# strain-gauge-amplifier-v1.net
KiCad netlist of a schematic drawn in EAGLE
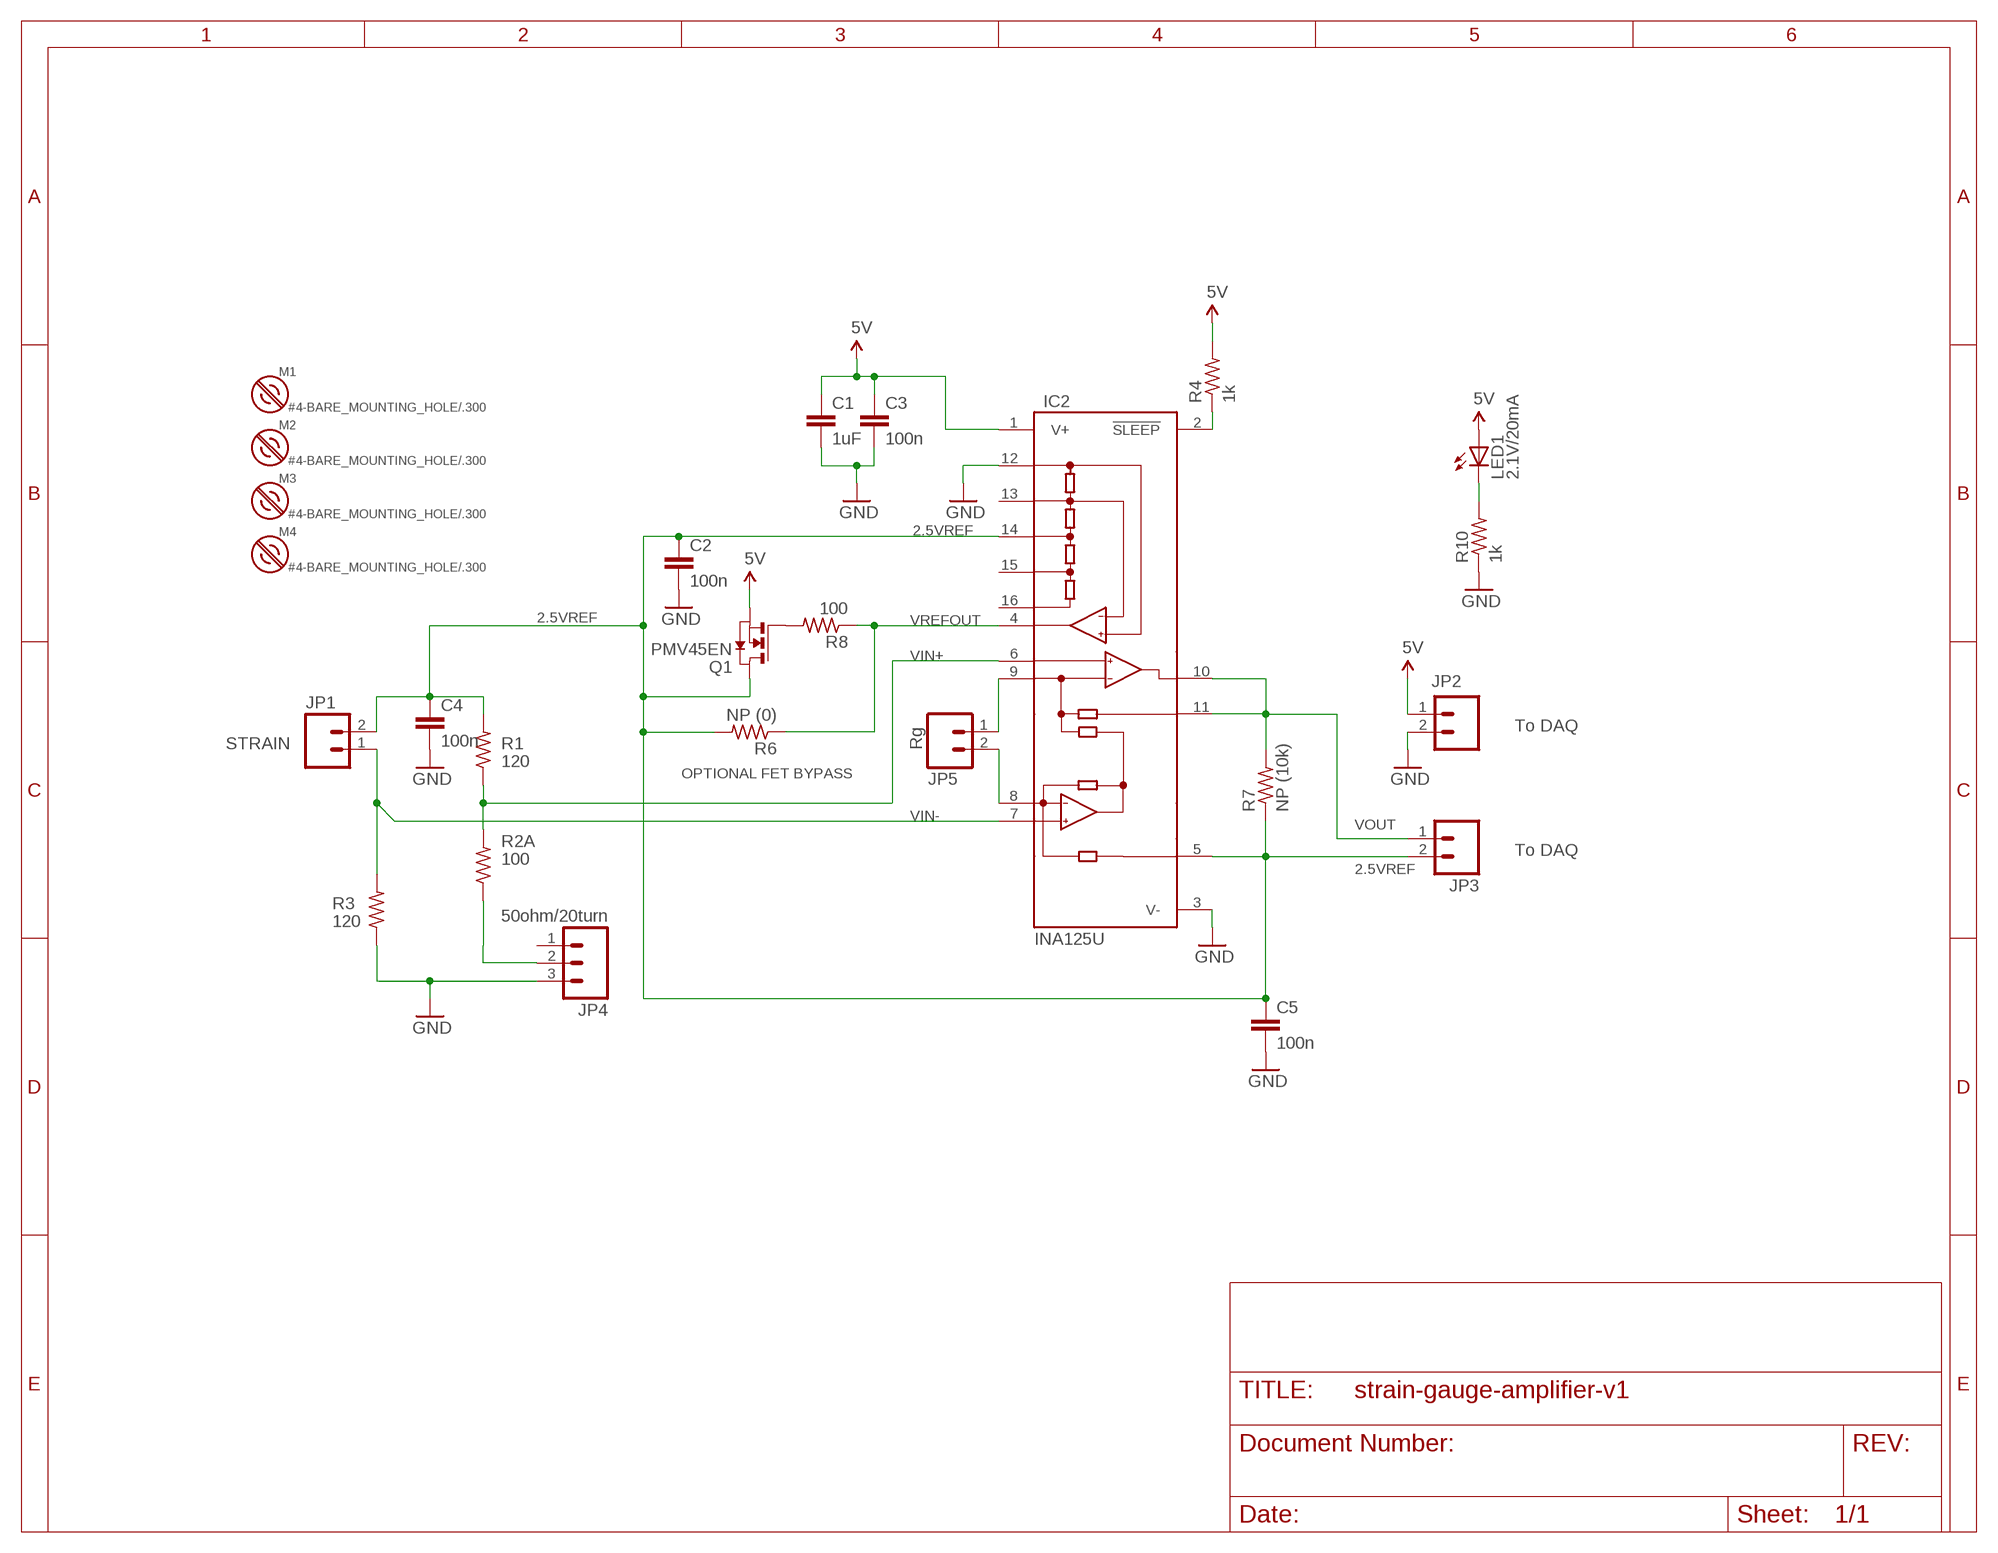
[diagram p0: schematic, sheet 1]

(export (version "E")
  (design (tool "Eeschema 10.0.6"))
  (components
    (comp (ref "C1")
      (value "1uF")
      (footprint "eagle-import:0805-C-NOSILK")
      (libsource (lib "eagle-import") (part "C-EU0805-C-NOSILK"))
    )
    (comp (ref "C2")
      (value "100n")
      (footprint "eagle-import:0805-C-NOSILK")
      (libsource (lib "eagle-import") (part "C-EU0805-C-NOSILK"))
    )
    (comp (ref "C3")
      (value "100n")
      (footprint "eagle-import:0805-C-NOSILK")
      (libsource (lib "eagle-import") (part "C-EU0805-C-NOSILK"))
    )
    (comp (ref "C4")
      (value "100n")
      (footprint "eagle-import:0805-C-NOSILK")
      (libsource (lib "eagle-import") (part "C-EU0805-C-NOSILK"))
    )
    (comp (ref "C5")
      (value "100n")
      (footprint "eagle-import:0805-C-NOSILK")
      (libsource (lib "eagle-import") (part "C-EU0805-C-NOSILK"))
    )
    (comp (ref "IC2")
      (value "INA125U")
      (footprint "eagle-import:SO16-1")
      (fields (field (name "MF") "TEXAS INSTRUMENT CONNECTORS"))
      (libsource (lib "eagle-import") (part "INA125U"))
    )
    (comp (ref "JP1")
      (value "STRAIN")
      (footprint "eagle-import:SCREWTERMINAL-5MM-2")
      (libsource (lib "eagle-import") (part "M025MM"))
    )
    (comp (ref "JP2")
      (value "M025MM")
      (footprint "eagle-import:SCREWTERMINAL-5MM-2")
      (libsource (lib "eagle-import") (part "M025MM"))
    )
    (comp (ref "JP3")
      (value "M025MM")
      (footprint "eagle-import:SCREWTERMINAL-5MM-2")
      (libsource (lib "eagle-import") (part "M025MM"))
    )
    (comp (ref "JP4")
      (value "50ohm/20turn")
      (footprint "eagle-import:1X03_NO_SILK")
      (libsource (lib "eagle-import") (part "M031X03_NO_SILK"))
    )
    (comp (ref "JP5")
      (value "Rg")
      (footprint "eagle-import:SCREWTERMINAL-5MM-2")
      (libsource (lib "eagle-import") (part "M025MM"))
    )
    (comp (ref "LED1")
      (value "2.1V/20mA")
      (footprint "eagle-import:LED-0603")
      (libsource (lib "eagle-import") (part "LED0603"))
    )
    (comp (ref "M1")
      (value "#4-BARE_MOUNTING_HOLE/.300")
      (footprint "eagle-import:#4_.300-BARE+STD_NUT_OR_STAR_WASHER")
      (libsource (lib "eagle-import") (part "#4-BARE_MOUNTING_HOLE/.300"))
    )
    (comp (ref "M2")
      (value "#4-BARE_MOUNTING_HOLE/.300")
      (footprint "eagle-import:#4_.300-BARE+STD_NUT_OR_STAR_WASHER")
      (libsource (lib "eagle-import") (part "#4-BARE_MOUNTING_HOLE/.300"))
    )
    (comp (ref "M3")
      (value "#4-BARE_MOUNTING_HOLE/.300")
      (footprint "eagle-import:#4_.300-BARE+STD_NUT_OR_STAR_WASHER")
      (libsource (lib "eagle-import") (part "#4-BARE_MOUNTING_HOLE/.300"))
    )
    (comp (ref "M4")
      (value "#4-BARE_MOUNTING_HOLE/.300")
      (footprint "eagle-import:#4_.300-BARE+STD_NUT_OR_STAR_WASHER")
      (libsource (lib "eagle-import") (part "#4-BARE_MOUNTING_HOLE/.300"))
    )
    (comp (ref "Q1")
      (value "PMV45EN")
      (footprint "eagle-import:SOT23")
      (libsource (lib "eagle-import") (part "PMV45EN"))
    )
    (comp (ref "R1")
      (value "120")
      (footprint "eagle-import:0805-C-NOSILK")
      (libsource (lib "eagle-import") (part "R-US_0805-C-NOSILK"))
    )
    (comp (ref "R2A")
      (value "100")
      (footprint "eagle-import:0805-C-NOSILK")
      (libsource (lib "eagle-import") (part "R-US_0805-C-NOSILK"))
    )
    (comp (ref "R3")
      (value "120")
      (footprint "eagle-import:0805-C-NOSILK")
      (libsource (lib "eagle-import") (part "R-US_0805-C-NOSILK"))
    )
    (comp (ref "R4")
      (value "1k")
      (footprint "eagle-import:0805-C-NOSILK")
      (libsource (lib "eagle-import") (part "R-US_0805-C-NOSILK"))
    )
    (comp (ref "R6")
      (value "NP (0)")
      (footprint "eagle-import:0805-C-NOSILK")
      (libsource (lib "eagle-import") (part "R-US_0805-C-NOSILK"))
    )
    (comp (ref "R7")
      (value "NP (10k)")
      (footprint "eagle-import:0805-C-NOSILK")
      (libsource (lib "eagle-import") (part "R-US_0805-C-NOSILK"))
    )
    (comp (ref "R8")
      (value "100")
      (footprint "eagle-import:0805-C-NOSILK")
      (libsource (lib "eagle-import") (part "R-US_0805-C-NOSILK"))
    )
    (comp (ref "R10")
      (value "1k")
      (footprint "eagle-import:0805-C-NOSILK")
      (libsource (lib "eagle-import") (part "R-US_0805-C-NOSILK"))
    )
  )
  (nets
    (net (code "1") (name "/2.5VREF") (class "Default")
      (node (ref "C2") (pin "1") (pinfunction "1_1") (pintype "passive"))
      (node (ref "C4") (pin "1") (pinfunction "1_1") (pintype "passive"))
      (node (ref "C5") (pin "1") (pinfunction "1_1") (pintype "passive"))
      (node (ref "IC2") (pin "14") (pinfunction "REF2.5_14") (pintype "output"))
      (node (ref "IC2") (pin "5") (pinfunction "REF_5") (pintype "passive"))
      (node (ref "JP1") (pin "2") (pinfunction "2_2") (pintype "passive"))
      (node (ref "JP3") (pin "2") (pinfunction "2_2") (pintype "passive"))
      (node (ref "Q1") (pin "3") (pinfunction "D_3") (pintype "passive"))
      (node (ref "R1") (pin "2") (pinfunction "2_2") (pintype "passive"))
      (node (ref "R6") (pin "2") (pinfunction "2_2") (pintype "passive"))
      (node (ref "R7") (pin "1") (pinfunction "1_1") (pintype "passive"))
    )
    (net (code "2") (name "/VIN+") (class "Default")
      (node (ref "IC2") (pin "6") (pinfunction "+IN_6") (pintype "input"))
      (node (ref "R1") (pin "1") (pinfunction "1_1") (pintype "passive"))
      (node (ref "R2A") (pin "2") (pinfunction "2_2") (pintype "passive"))
    )
    (net (code "3") (name "/VIN-") (class "Default")
      (node (ref "IC2") (pin "7") (pinfunction "-VIN_7") (pintype "input"))
      (node (ref "JP1") (pin "1") (pinfunction "1_1") (pintype "passive"))
      (node (ref "R3") (pin "2") (pinfunction "2_2") (pintype "passive"))
    )
    (net (code "4") (name "/VOUT") (class "Default")
      (node (ref "IC2") (pin "10") (pinfunction "OUT_10") (pintype "output"))
      (node (ref "IC2") (pin "11") (pinfunction "SENSE_11") (pintype "passive"))
      (node (ref "JP3") (pin "1") (pinfunction "1_1") (pintype "passive"))
      (node (ref "R7") (pin "2") (pinfunction "2_2") (pintype "passive"))
    )
    (net (code "5") (name "/VREFOUT") (class "Default")
      (node (ref "IC2") (pin "4") (pinfunction "REFOUT_4") (pintype "output"))
      (node (ref "R6") (pin "1") (pinfunction "1_1") (pintype "passive"))
      (node (ref "R8") (pin "1") (pinfunction "1_1") (pintype "passive"))
    )
    (net (code "6") (name "5V") (class "Default")
      (node (ref "C1") (pin "1") (pinfunction "1_1") (pintype "passive"))
      (node (ref "C3") (pin "1") (pinfunction "1_1") (pintype "passive"))
      (node (ref "IC2") (pin "1") (pinfunction "V+_1") (pintype "power_in"))
      (node (ref "JP2") (pin "1") (pinfunction "1_1") (pintype "passive"))
      (node (ref "LED1") (pin "A") (pinfunction "A_A") (pintype "passive"))
      (node (ref "Q1") (pin "2") (pinfunction "S_2") (pintype "passive"))
      (node (ref "R4") (pin "2") (pinfunction "2_2") (pintype "passive"))
    )
    (net (code "7") (name "GND") (class "Default")
      (node (ref "C1") (pin "2") (pinfunction "2_2") (pintype "passive"))
      (node (ref "C2") (pin "2") (pinfunction "2_2") (pintype "passive"))
      (node (ref "C3") (pin "2") (pinfunction "2_2") (pintype "passive"))
      (node (ref "C4") (pin "2") (pinfunction "2_2") (pintype "passive"))
      (node (ref "C5") (pin "2") (pinfunction "2_2") (pintype "passive"))
      (node (ref "IC2") (pin "12") (pinfunction "REFCOM_12") (pintype "passive"))
      (node (ref "IC2") (pin "3") (pinfunction "V-_3") (pintype "power_in"))
      (node (ref "JP2") (pin "2") (pinfunction "2_2") (pintype "passive"))
      (node (ref "JP4") (pin "3") (pinfunction "3_3") (pintype "passive"))
      (node (ref "R10") (pin "1") (pinfunction "1_1") (pintype "passive"))
      (node (ref "R3") (pin "1") (pinfunction "1_1") (pintype "passive"))
    )
    (net (code "8") (name "Net-(IC2-RG-Pad8)") (class "Default")
      (node (ref "IC2") (pin "8") (pinfunction "RG_8") (pintype "passive"))
      (node (ref "JP5") (pin "2") (pinfunction "2_2") (pintype "passive"))
    )
    (net (code "9") (name "Net-(IC2-RG-Pad9)") (class "Default")
      (node (ref "IC2") (pin "9") (pinfunction "RG_9") (pintype "passive"))
      (node (ref "JP5") (pin "1") (pinfunction "1_1") (pintype "passive"))
    )
    (net (code "10") (name "Net-(IC2-~{SLEEP})") (class "Default")
      (node (ref "IC2") (pin "2") (pinfunction "~{SLEEP}_2") (pintype "input"))
      (node (ref "R4") (pin "1") (pinfunction "1_1") (pintype "passive"))
    )
    (net (code "11") (name "Net-(JP4-Pad2)") (class "Default")
      (node (ref "JP4") (pin "2") (pinfunction "2_2") (pintype "passive"))
      (node (ref "R2A") (pin "1") (pinfunction "1_1") (pintype "passive"))
    )
    (net (code "12") (name "Net-(LED1-PadC)") (class "Default")
      (node (ref "LED1") (pin "C") (pinfunction "C_C") (pintype "passive"))
      (node (ref "R10") (pin "2") (pinfunction "2_2") (pintype "passive"))
    )
    (net (code "13") (name "Net-(Q1-G)") (class "Default")
      (node (ref "Q1") (pin "1") (pinfunction "G_1") (pintype "passive"))
      (node (ref "R8") (pin "2") (pinfunction "2_2") (pintype "passive"))
    )
    (net (code "14") (name "unconnected-(IC2-REF5-Pad15)") (class "Default")
      (node (ref "IC2") (pin "15") (pinfunction "REF5_15") (pintype "output"))
    )
    (net (code "15") (name "unconnected-(IC2-REF10-Pad16)") (class "Default")
      (node (ref "IC2") (pin "16") (pinfunction "REF10_16") (pintype "output"))
    )
    (net (code "16") (name "unconnected-(IC2-REFBG-Pad13)") (class "Default")
      (node (ref "IC2") (pin "13") (pinfunction "REFBG_13") (pintype "output"))
    )
    (net (code "17") (name "unconnected-(JP4-Pad1)") (class "Default")
      (node (ref "JP4") (pin "1") (pinfunction "1_1") (pintype "passive"))
    )
  )
)
